# nfc.net
KiCad netlist of a schematic drawn in Altium Designer
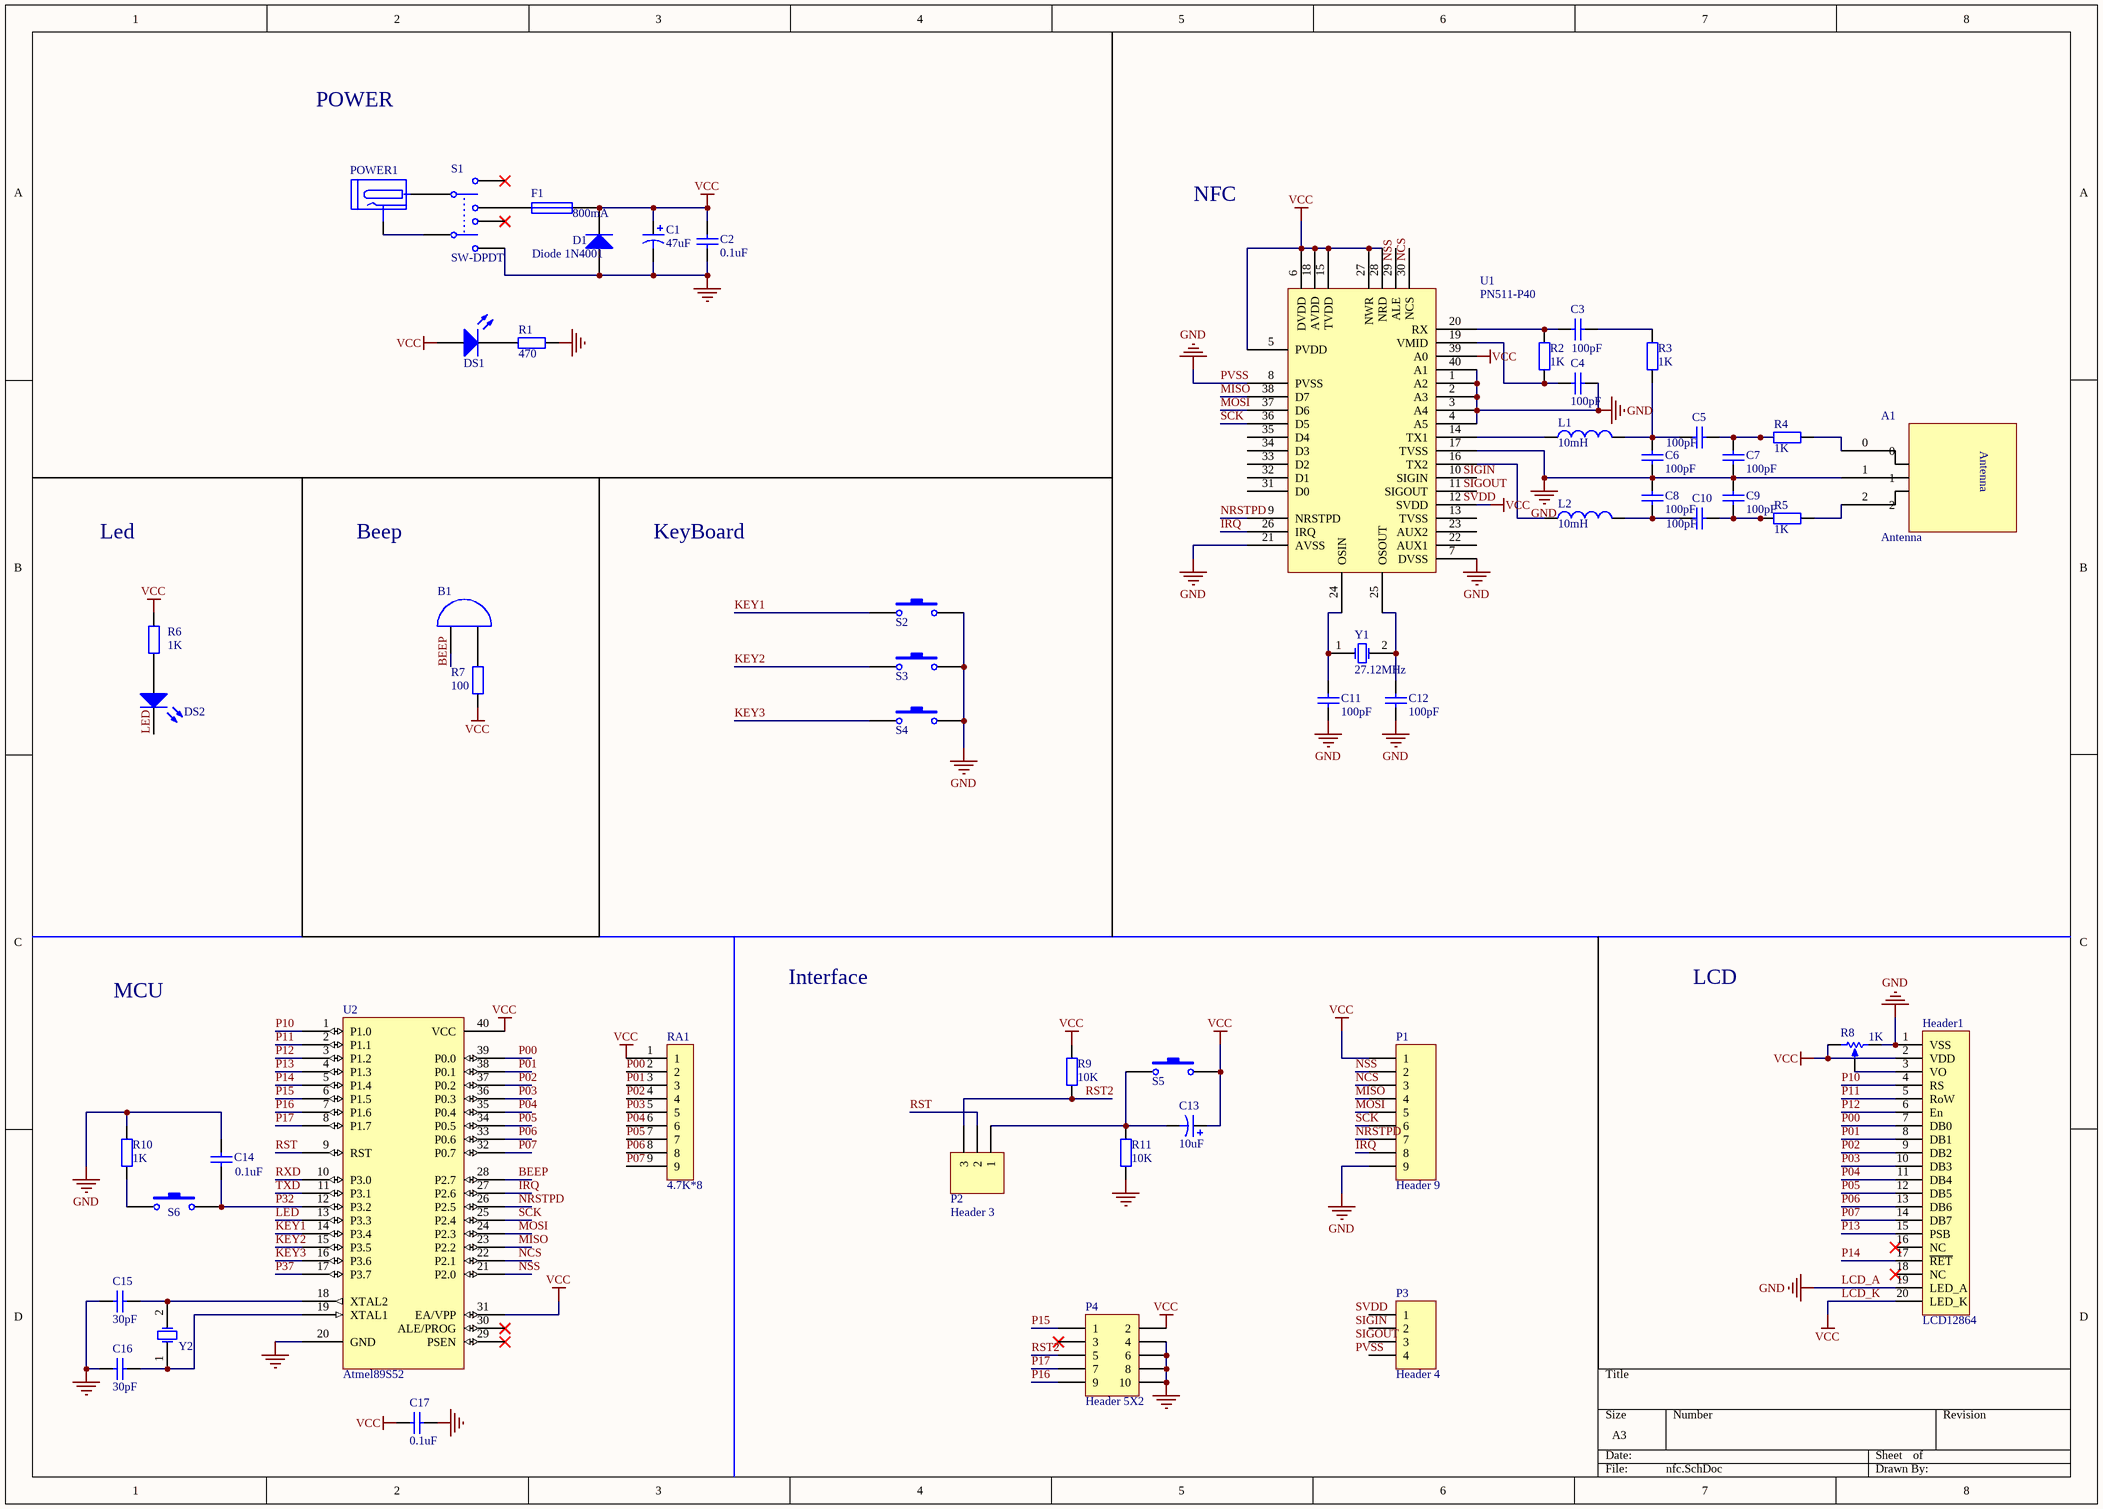
[diagram p0: nfc.SchDoc]

(export (version "E")
  (design (tool "Eeschema 10.0.6"))
  (components
    (comp (ref "A1") (value "Antenna") (libsource (lib "*") (part "Antenna")))
    (comp (ref "B1") (value "BEEP") (footprint "Buzzer") (libsource (lib "51ExpBoard") (part "BEEP")))
    (comp (ref "C1")
      (value "47uF")
      (footprint "51ExpBoard:CAP-LED")
      (description "Polarized Capacitor (Axial)")
      (fields (field (name "Comment") "CAP POL") (field (name "PUBLISHER") "Altium Limited"))
      (libsource (lib "51ExpBoard") (part "CAP POL"))
    )
    (comp (ref "C2")
      (value "0.1uF")
      (footprint "51ExpBoard:CAP")
      (description "Capacitor")
      (fields (field (name "Comment") "Cap") (field (name "PUBLISHER") "Altium Limited"))
      (libsource (lib "51ExpBoard") (part "Cap"))
    )
    (comp (ref "C3")
      (value "100pF")
      (footprint "RAD-0.3")
      (description "Capacitor")
      (fields (field (name "Comment") "Cap") (field (name "PUBLISHER") "Altium Limited"))
      (libsource (lib "Miscellaneous Devices") (part "Cap"))
    )
    (comp (ref "C4")
      (value "100pF")
      (footprint "RAD-0.3")
      (description "Capacitor")
      (fields (field (name "Comment") "Cap") (field (name "PUBLISHER") "Altium Limited"))
      (libsource (lib "Miscellaneous Devices") (part "Cap"))
    )
    (comp (ref "C5")
      (value "100pF")
      (footprint "RAD-0.3")
      (description "Capacitor")
      (fields (field (name "Comment") "Cap") (field (name "PUBLISHER") "Altium Limited"))
      (libsource (lib "Miscellaneous Devices") (part "Cap"))
    )
    (comp (ref "C6")
      (value "100pF")
      (footprint "RAD-0.3")
      (description "Capacitor")
      (fields (field (name "Comment") "Cap") (field (name "PUBLISHER") "Altium Limited"))
      (libsource (lib "Miscellaneous Devices") (part "Cap"))
    )
    (comp (ref "C7")
      (value "100pF")
      (footprint "RAD-0.3")
      (description "Capacitor")
      (fields (field (name "Comment") "Cap") (field (name "PUBLISHER") "Altium Limited"))
      (libsource (lib "Miscellaneous Devices") (part "Cap"))
    )
    (comp (ref "C8")
      (value "100pF")
      (footprint "RAD-0.3")
      (description "Capacitor")
      (fields (field (name "Comment") "Cap") (field (name "PUBLISHER") "Altium Limited"))
      (libsource (lib "Miscellaneous Devices") (part "Cap"))
    )
    (comp (ref "C9")
      (value "100pF")
      (footprint "RAD-0.3")
      (description "Capacitor")
      (fields (field (name "Comment") "Cap") (field (name "PUBLISHER") "Altium Limited"))
      (libsource (lib "Miscellaneous Devices") (part "Cap"))
    )
    (comp (ref "C10")
      (value "100pF")
      (footprint "RAD-0.3")
      (description "Capacitor")
      (fields (field (name "Comment") "Cap") (field (name "PUBLISHER") "Altium Limited"))
      (libsource (lib "Miscellaneous Devices") (part "Cap"))
    )
    (comp (ref "C11")
      (value "100pF")
      (footprint "RAD-0.3")
      (description "Capacitor")
      (fields (field (name "Comment") "Cap") (field (name "PUBLISHER") "Altium Limited"))
      (libsource (lib "Miscellaneous Devices") (part "Cap"))
    )
    (comp (ref "C12")
      (value "100pF")
      (footprint "RAD-0.3")
      (description "Capacitor")
      (fields (field (name "Comment") "Cap") (field (name "PUBLISHER") "Altium Limited"))
      (libsource (lib "Miscellaneous Devices") (part "Cap"))
    )
    (comp (ref "C13")
      (value "10uF")
      (footprint "51ExpBoard:CAP-LED")
      (description "Polarized Capacitor (Axial)")
      (fields (field (name "Comment") "CAP POL") (field (name "PUBLISHER") "Altium Limited"))
      (libsource (lib "51ExpBoard") (part "CAP POL"))
    )
    (comp (ref "C14")
      (value "0.1uF")
      (footprint "VP32-3.2")
      (description "Capacitor")
      (fields (field (name "Comment") "Cap") (field (name "PUBLISHER") "Altium Limited"))
      (libsource (lib "Miscellaneous Devices") (part "Cap"))
    )
    (comp (ref "C15")
      (value "30pF")
      (footprint "51ExpBoard:CAP")
      (description "Capacitor")
      (fields (field (name "Comment") "Cap") (field (name "PUBLISHER") "Altium Limited"))
      (libsource (lib "51ExpBoard") (part "Cap"))
    )
    (comp (ref "C16")
      (value "30pF")
      (footprint "51ExpBoard:CAP")
      (description "Capacitor")
      (fields (field (name "Comment") "Cap") (field (name "PUBLISHER") "Altium Limited"))
      (libsource (lib "51ExpBoard") (part "Cap"))
    )
    (comp (ref "C17")
      (value "0.1uF")
      (footprint "VP32-3.2")
      (description "Capacitor")
      (fields (field (name "Comment") "Cap") (field (name "PUBLISHER") "Altium Limited"))
      (libsource (lib "Miscellaneous Devices") (part "Cap"))
    )
    (comp (ref "D1")
      (value "Diode 1N4001")
      (footprint "DIODE-0.4")
      (description "1 Amp General Purpose Rectifier")
      (fields (field (name "PUBLISHER") "Altium Limited"))
      (libsource (lib "51ExpBoard") (part "Diode 1N4001"))
    )
    (comp (ref "DS1") (value "LED") (footprint "CAP-LED") (libsource (lib "51ExpBoard") (part "LED")))
    (comp (ref "DS2") (value "LED") (footprint "CAP-LED") (libsource (lib "51ExpBoard") (part "LED")))
    (comp (ref "F1")
      (value "800mA")
      (footprint "AXIAL-0.3")
      (fields (field (name "Comment") "FUSE1"))
      (libsource (lib "51ExpBoard") (part "FUSE1"))
    )
    (comp (ref "Header1") (value "LCD12864") (libsource (lib "nfc") (part "LCD12864")))
    (comp (ref "L1")
      (value "10mH")
      (footprint "0402-A")
      (description "Inductor")
      (fields (field (name "PUBLISHER") "Altium Limited"))
      (libsource (lib "Miscellaneous Devices") (part "Inductor"))
    )
    (comp (ref "L2")
      (value "10mH")
      (footprint "0402-A")
      (description "Inductor")
      (fields (field (name "PUBLISHER") "Altium Limited"))
      (libsource (lib "Miscellaneous Devices") (part "Inductor"))
    )
    (comp (ref "P1")
      (value "Header 9")
      (footprint "HDR1X9")
      (description "Header, 9-Pin")
      (fields (field (name "PUBLISHER") "Altium Limited"))
      (libsource (lib "Miscellaneous Connectors") (part "Header 9"))
    )
    (comp (ref "P2")
      (value "Header 3")
      (footprint "HDR1X3")
      (description "Header, 3-Pin")
      (fields (field (name "PUBLISHER") "Altium Limited"))
      (libsource (lib "Miscellaneous Connectors") (part "Header 3"))
    )
    (comp (ref "P3")
      (value "Header 4")
      (footprint "HDR1X4")
      (description "Header, 4-Pin")
      (fields (field (name "PUBLISHER") "Altium Limited"))
      (libsource (lib "Miscellaneous Connectors") (part "Header 4"))
    )
    (comp (ref "P4")
      (value "Header 5X2")
      (footprint "HDR2X5")
      (description "Header, 5-Pin, Dual row")
      (fields (field (name "PUBLISHER") "Altium Limited"))
      (libsource (lib "Miscellaneous Connectors") (part "Header 5X2"))
    )
    (comp (ref "POWER1") (value "POWER") (footprint "Power") (libsource (lib "51ExpBoard") (part "POWER")))
    (comp (ref "R1")
      (value "470")
      (footprint "AXIAL-0.4")
      (description "Resistor")
      (fields (field (name "Comment") "RES") (field (name "PUBLISHER") "Altium Limited"))
      (libsource (lib "") (part "RES_2"))
    )
    (comp (ref "R2")
      (value "1K")
      (footprint "AXIAL-0.4")
      (description "Resistor")
      (fields (field (name "Comment") "Res2") (field (name "PUBLISHER") "Altium Limited"))
      (libsource (lib "Miscellaneous Devices") (part "Res2"))
    )
    (comp (ref "R3")
      (value "1K")
      (footprint "AXIAL-0.4")
      (description "Resistor")
      (fields (field (name "Comment") "Res2") (field (name "PUBLISHER") "Altium Limited"))
      (libsource (lib "Miscellaneous Devices") (part "Res2"))
    )
    (comp (ref "R4")
      (value "1K")
      (footprint "AXIAL-0.4")
      (description "Resistor")
      (fields (field (name "Comment") "Res2") (field (name "PUBLISHER") "Altium Limited"))
      (libsource (lib "") (part "Res2_1"))
    )
    (comp (ref "R5")
      (value "1K")
      (footprint "AXIAL-0.4")
      (description "Resistor")
      (fields (field (name "Comment") "Res2") (field (name "PUBLISHER") "Altium Limited"))
      (libsource (lib "") (part "Res2_1"))
    )
    (comp (ref "R6")
      (value "1K")
      (footprint "AXIAL-0.4")
      (description "Resistor")
      (fields (field (name "Comment") "RES") (field (name "PUBLISHER") "Altium Limited"))
      (libsource (lib "51ExpBoard") (part "RES"))
    )
    (comp (ref "R7")
      (value "100")
      (footprint "AXIAL-0.4")
      (description "Resistor")
      (fields (field (name "Comment") "RES") (field (name "PUBLISHER") "Altium Limited"))
      (libsource (lib "") (part "RES_1"))
    )
    (comp (ref "R8")
      (value "1K")
      (footprint "VR5")
      (description "Potentiometer")
      (fields (field (name "Comment") "RPot") (field (name "PUBLISHER") "Altium Limited"))
      (libsource (lib "Miscellaneous Devices") (part "RPot"))
    )
    (comp (ref "R9")
      (value "10K")
      (footprint "AXIAL-0.4")
      (description "Resistor")
      (fields (field (name "Comment") "RES") (field (name "PUBLISHER") "Altium Limited"))
      (libsource (lib "") (part "RES_1"))
    )
    (comp (ref "R10")
      (value "1K")
      (footprint "AXIAL-0.4")
      (description "Resistor")
      (fields (field (name "Comment") "RES") (field (name "PUBLISHER") "Altium Limited"))
      (libsource (lib "51ExpBoard") (part "RES"))
    )
    (comp (ref "R11")
      (value "10K")
      (footprint "AXIAL-0.4")
      (description "Resistor")
      (fields (field (name "Comment") "RES") (field (name "PUBLISHER") "Altium Limited"))
      (libsource (lib "51ExpBoard") (part "RES"))
    )
    (comp (ref "RA1")
      (value "4.7K*8")
      (footprint "HDR1X9")
      (fields (field (name "Comment") "Res Arry"))
      (libsource (lib "51ExpBoard") (part "Res Arry"))
    )
    (comp (ref "S1")
      (value "SW-DPDT")
      (footprint "SWITCH-6")
      (description "Double-Pole, Double-Throw Switch")
      (fields (field (name "PUBLISHER") "Altium Limited"))
      (libsource (lib "51ExpBoard") (part "SW-DPDT"))
    )
    (comp (ref "S2") (value "SW-PB") (footprint "key") (libsource (lib "51ExpBoard") (part "SW-PB")))
    (comp (ref "S3") (value "SW-PB") (footprint "key") (libsource (lib "51ExpBoard") (part "SW-PB")))
    (comp (ref "S4") (value "SW-PB") (footprint "key") (libsource (lib "51ExpBoard") (part "SW-PB")))
    (comp (ref "S5") (value "SW-PB") (footprint "key") (libsource (lib "51ExpBoard") (part "SW-PB")))
    (comp (ref "S6") (value "SW-PB") (footprint "key") (libsource (lib "51ExpBoard") (part "SW-PB")))
    (comp (ref "U1") (value "PN511-P40") (libsource (lib "*") (part "PN511-P40")))
    (comp (ref "U2")
      (value "Atmel89S52")
      (footprint "ATMEL89S52-DIP40")
      (libsource (lib "51ExpBoard") (part "Atmel89S52"))
    )
    (comp (ref "Y1")
      (value "27.12MHz")
      (footprint "R38")
      (description "Crystal Oscillator")
      (fields (field (name "PUBLISHER") "Altium Limited"))
      (libsource (lib "Miscellaneous Devices") (part "XTAL"))
    )
    (comp (ref "Y2")
      (value "XTAL")
      (footprint "XTAL")
      (description "Crystal Oscillator")
      (fields (field (name "PUBLISHER") "Altium Limited"))
      (libsource (lib "51ExpBoard") (part "XTAL"))
    )
  )
  (nets
    (net (code "1") (name "/BEEP") (class "Default")
      (node (ref "B1") (pin "2") (pinfunction "A_2") (pintype "passive"))
      (node (ref "U2") (pin "28") (pinfunction "P2.7_28") (pintype "bidirectional"))
    )
    (net (code "2") (name "/IRQ") (class "Default")
      (node (ref "P1") (pin "8") (pinfunction "8_8") (pintype "passive"))
      (node (ref "U1") (pin "26") (pinfunction "IRQ_26") (pintype "passive"))
      (node (ref "U2") (pin "27") (pinfunction "P2.6_27") (pintype "bidirectional"))
    )
    (net (code "3") (name "/KEY1") (class "Default")
      (node (ref "S2") (pin "1") (pinfunction "1_1") (pintype "passive"))
      (node (ref "U2") (pin "14") (pinfunction "P3.4_14") (pintype "bidirectional"))
    )
    (net (code "4") (name "/KEY2") (class "Default")
      (node (ref "S3") (pin "1") (pinfunction "1_1") (pintype "passive"))
      (node (ref "U2") (pin "15") (pinfunction "P3.5_15") (pintype "bidirectional"))
    )
    (net (code "5") (name "/KEY3") (class "Default")
      (node (ref "S4") (pin "1") (pinfunction "1_1") (pintype "passive"))
      (node (ref "U2") (pin "16") (pinfunction "P3.6_16") (pintype "bidirectional"))
    )
    (net (code "6") (name "/LED") (class "Default")
      (node (ref "DS2") (pin "2") (pinfunction "K_2") (pintype "passive"))
      (node (ref "U2") (pin "13") (pinfunction "P3.3_13") (pintype "bidirectional"))
    )
    (net (code "7") (name "/MISO") (class "Default")
      (node (ref "P1") (pin "4") (pinfunction "4_4") (pintype "passive"))
      (node (ref "U1") (pin "38") (pinfunction "D7_38") (pintype "passive"))
      (node (ref "U2") (pin "23") (pinfunction "P2.2_23") (pintype "bidirectional"))
    )
    (net (code "8") (name "/MOSI") (class "Default")
      (node (ref "P1") (pin "5") (pinfunction "5_5") (pintype "passive"))
      (node (ref "U1") (pin "37") (pinfunction "D6_37") (pintype "passive"))
      (node (ref "U2") (pin "24") (pinfunction "P2.3_24") (pintype "bidirectional"))
    )
    (net (code "9") (name "/NCS") (class "Default")
      (node (ref "P1") (pin "3") (pinfunction "3_3") (pintype "passive"))
      (node (ref "U2") (pin "22") (pinfunction "P2.1_22") (pintype "bidirectional"))
    )
    (net (code "10") (name "/NRSTPD") (class "Default")
      (node (ref "P1") (pin "7") (pinfunction "7_7") (pintype "passive"))
      (node (ref "U1") (pin "9") (pinfunction "NRSTPD_9") (pintype "passive"))
      (node (ref "U2") (pin "26") (pinfunction "P2.5_26") (pintype "bidirectional"))
    )
    (net (code "11") (name "/NSS") (class "Default")
      (node (ref "P1") (pin "2") (pinfunction "2_2") (pintype "passive"))
      (node (ref "U2") (pin "21") (pinfunction "P2.0_21") (pintype "bidirectional"))
    )
    (net (code "12") (name "/P00") (class "Default")
      (node (ref "Header1") (pin "7") (pinfunction "DB0_7") (pintype "passive"))
      (node (ref "RA1") (pin "2") (pinfunction "2_2") (pintype "passive"))
      (node (ref "U2") (pin "39") (pinfunction "P0.0_39") (pintype "bidirectional"))
    )
    (net (code "13") (name "/P01") (class "Default")
      (node (ref "Header1") (pin "8") (pinfunction "DB1_8") (pintype "passive"))
      (node (ref "RA1") (pin "3") (pinfunction "3_3") (pintype "passive"))
      (node (ref "U2") (pin "38") (pinfunction "P0.1_38") (pintype "bidirectional"))
    )
    (net (code "14") (name "/P02") (class "Default")
      (node (ref "Header1") (pin "9") (pinfunction "DB2_9") (pintype "passive"))
      (node (ref "RA1") (pin "4") (pinfunction "4_4") (pintype "passive"))
      (node (ref "U2") (pin "37") (pinfunction "P0.2_37") (pintype "bidirectional"))
    )
    (net (code "15") (name "/P03") (class "Default")
      (node (ref "Header1") (pin "10") (pinfunction "DB3_10") (pintype "passive"))
      (node (ref "RA1") (pin "5") (pinfunction "5_5") (pintype "passive"))
      (node (ref "U2") (pin "36") (pinfunction "P0.3_36") (pintype "bidirectional"))
    )
    (net (code "16") (name "/P04") (class "Default")
      (node (ref "Header1") (pin "11") (pinfunction "DB4_11") (pintype "passive"))
      (node (ref "RA1") (pin "6") (pinfunction "6_6") (pintype "passive"))
      (node (ref "U2") (pin "35") (pinfunction "P0.4_35") (pintype "bidirectional"))
    )
    (net (code "17") (name "/P05") (class "Default")
      (node (ref "Header1") (pin "12") (pinfunction "DB5_12") (pintype "passive"))
      (node (ref "RA1") (pin "7") (pinfunction "7_7") (pintype "passive"))
      (node (ref "U2") (pin "34") (pinfunction "P0.5_34") (pintype "bidirectional"))
    )
    (net (code "18") (name "/P06") (class "Default")
      (node (ref "Header1") (pin "13") (pinfunction "DB6_13") (pintype "passive"))
      (node (ref "RA1") (pin "8") (pinfunction "8_8") (pintype "passive"))
      (node (ref "U2") (pin "33") (pinfunction "P0.6_33") (pintype "bidirectional"))
    )
    (net (code "19") (name "/P07") (class "Default")
      (node (ref "Header1") (pin "14") (pinfunction "DB7_14") (pintype "passive"))
      (node (ref "RA1") (pin "9") (pinfunction "9_9") (pintype "passive"))
      (node (ref "U2") (pin "32") (pinfunction "P0.7_32") (pintype "bidirectional"))
    )
    (net (code "20") (name "/P10") (class "Default")
      (node (ref "Header1") (pin "4") (pinfunction "RS_4") (pintype "passive"))
      (node (ref "U2") (pin "1") (pinfunction "P1.0_1") (pintype "bidirectional"))
    )
    (net (code "21") (name "/P11") (class "Default")
      (node (ref "Header1") (pin "5") (pinfunction "RoW_5") (pintype "passive"))
      (node (ref "U2") (pin "2") (pinfunction "P1.1_2") (pintype "bidirectional"))
    )
    (net (code "22") (name "/P12") (class "Default")
      (node (ref "Header1") (pin "6") (pinfunction "En_6") (pintype "passive"))
      (node (ref "U2") (pin "3") (pinfunction "P1.2_3") (pintype "bidirectional"))
    )
    (net (code "23") (name "/P13") (class "Default")
      (node (ref "Header1") (pin "15") (pinfunction "PSB_15") (pintype "passive"))
      (node (ref "U2") (pin "4") (pinfunction "P1.3_4") (pintype "bidirectional"))
    )
    (net (code "24") (name "/P14") (class "Default")
      (node (ref "Header1") (pin "17") (pinfunction "~{RET}_17") (pintype "passive"))
      (node (ref "U2") (pin "5") (pinfunction "P1.4_5") (pintype "bidirectional"))
    )
    (net (code "25") (name "/P15") (class "Default")
      (node (ref "P4") (pin "1") (pinfunction "1_1") (pintype "passive"))
      (node (ref "U2") (pin "6") (pinfunction "P1.5_6") (pintype "bidirectional"))
    )
    (net (code "26") (name "/P16") (class "Default")
      (node (ref "P4") (pin "9") (pinfunction "9_9") (pintype "passive"))
      (node (ref "U2") (pin "7") (pinfunction "P1.6_7") (pintype "bidirectional"))
    )
    (net (code "27") (name "/P17") (class "Default")
      (node (ref "P4") (pin "7") (pinfunction "7_7") (pintype "passive"))
      (node (ref "U2") (pin "8") (pinfunction "P1.7_8") (pintype "bidirectional"))
    )
    (net (code "28") (name "/P32") (class "Default")
      (node (ref "C14") (pin "1") (pinfunction "1_1") (pintype "passive"))
      (node (ref "S6") (pin "2") (pinfunction "2_2") (pintype "passive"))
      (node (ref "U2") (pin "12") (pinfunction "P3.2_12") (pintype "bidirectional"))
    )
    (net (code "29") (name "/P37") (class "Default")
      (node (ref "U2") (pin "17") (pinfunction "P3.7_17") (pintype "bidirectional"))
    )
    (net (code "30") (name "/RST") (class "Default")
      (node (ref "P2") (pin "2") (pinfunction "2_2") (pintype "passive"))
      (node (ref "U2") (pin "9") (pinfunction "RST_9") (pintype "bidirectional"))
    )
    (net (code "31") (name "/RST2") (class "Default")
      (node (ref "P2") (pin "3") (pinfunction "3_3") (pintype "passive"))
      (node (ref "P4") (pin "5") (pinfunction "5_5") (pintype "passive"))
      (node (ref "R9") (pin "2") (pinfunction "2_2") (pintype "passive"))
    )
    (net (code "32") (name "/RXD") (class "Default")
      (node (ref "U2") (pin "10") (pinfunction "P3.0_10") (pintype "bidirectional"))
    )
    (net (code "33") (name "/SCK") (class "Default")
      (node (ref "P1") (pin "6") (pinfunction "6_6") (pintype "passive"))
      (node (ref "U1") (pin "36") (pinfunction "D5_36") (pintype "passive"))
      (node (ref "U2") (pin "25") (pinfunction "P2.4_25") (pintype "bidirectional"))
    )
    (net (code "37") (name "/TXD") (class "Default")
      (node (ref "U2") (pin "11") (pinfunction "P3.1_11") (pintype "bidirectional"))
    )
    (net (code "38") (name "GND") (class "Default")
      (node (ref "A1") (pin "1") (pinfunction "1_1") (pintype "passive"))
      (node (ref "C1") (pin "2") (pinfunction "2_2") (pintype "passive"))
      (node (ref "C11") (pin "1") (pinfunction "1_1") (pintype "passive"))
      (node (ref "C12") (pin "1") (pinfunction "1_1") (pintype "passive"))
      (node (ref "C14") (pin "2") (pinfunction "2_2") (pintype "passive"))
      (node (ref "C15") (pin "1") (pinfunction "1_1") (pintype "passive"))
      (node (ref "C16") (pin "1") (pinfunction "1_1") (pintype "passive"))
      (node (ref "C17") (pin "2") (pinfunction "2_2") (pintype "passive"))
      (node (ref "C2") (pin "2") (pinfunction "2_2") (pintype "passive"))
      (node (ref "C4") (pin "2") (pinfunction "2_2") (pintype "passive"))
      (node (ref "C6") (pin "1") (pinfunction "1_1") (pintype "passive"))
      (node (ref "C7") (pin "1") (pinfunction "1_1") (pintype "passive"))
      (node (ref "C8") (pin "2") (pinfunction "2_2") (pintype "passive"))
      (node (ref "C9") (pin "2") (pinfunction "2_2") (pintype "passive"))
      (node (ref "D1") (pin "1") (pinfunction "A_1") (pintype "passive"))
      (node (ref "Header1") (pin "1") (pinfunction "VSS_1") (pintype "passive"))
      (node (ref "Header1") (pin "19") (pinfunction "LED_A_19") (pintype "passive"))
      (node (ref "P1") (pin "9") (pinfunction "9_9") (pintype "passive"))
      (node (ref "P4") (pin "10") (pinfunction "10_10") (pintype "passive"))
      (node (ref "P4") (pin "4") (pinfunction "4_4") (pintype "passive"))
      (node (ref "P4") (pin "6") (pinfunction "6_6") (pintype "passive"))
      (node (ref "P4") (pin "8") (pinfunction "8_8") (pintype "passive"))
      (node (ref "R1") (pin "2") (pinfunction "2_2") (pintype "passive"))
      (node (ref "R10") (pin "2") (pinfunction "2_2") (pintype "passive"))
      (node (ref "R11") (pin "1") (pinfunction "1_1") (pintype "passive"))
      (node (ref "R8") (pin "2") (pinfunction "BOT_2") (pintype "passive"))
      (node (ref "S1") (pin "6") (pinfunction "6_6") (pintype "passive"))
      (node (ref "S2") (pin "2") (pinfunction "2_2") (pintype "passive"))
      (node (ref "S3") (pin "2") (pinfunction "2_2") (pintype "passive"))
      (node (ref "S4") (pin "2") (pinfunction "2_2") (pintype "passive"))
      (node (ref "U1") (pin "1") (pinfunction "A2_1") (pintype "passive"))
      (node (ref "U1") (pin "17") (pinfunction "TVSS_17") (pintype "passive"))
      (node (ref "U1") (pin "2") (pinfunction "A3_2") (pintype "passive"))
      (node (ref "U1") (pin "21") (pinfunction "AVSS_21") (pintype "passive"))
      (node (ref "U1") (pin "3") (pinfunction "A4_3") (pintype "passive"))
      (node (ref "U1") (pin "4") (pinfunction "A5_4") (pintype "passive"))
      (node (ref "U1") (pin "40") (pinfunction "A1_40") (pintype "passive"))
      (node (ref "U1") (pin "7") (pinfunction "DVSS_7") (pintype "passive"))
      (node (ref "U1") (pin "8") (pinfunction "PVSS_8") (pintype "passive"))
      (node (ref "U2") (pin "20") (pinfunction "GND_20") (pintype "power_in"))
    )
    (net (code "39") (name "Net-(A1-Pad0)") (class "Default")
      (node (ref "A1") (pin "0") (pinfunction "0_0") (pintype "passive"))
      (node (ref "R4") (pin "1") (pinfunction "1_1") (pintype "passive"))
    )
    (net (code "40") (name "Net-(A1-Pad2)") (class "Default")
      (node (ref "A1") (pin "2") (pinfunction "2_2") (pintype "passive"))
      (node (ref "R5") (pin "1") (pinfunction "1_1") (pintype "passive"))
    )
    (net (code "41") (name "Net-(B1-B)") (class "Default")
      (node (ref "B1") (pin "1") (pinfunction "B_1") (pintype "passive"))
      (node (ref "R7") (pin "1") (pinfunction "1_1") (pintype "passive"))
    )
    (net (code "42") (name "Net-(C3-Pad2)") (class "Default")
      (node (ref "C3") (pin "2") (pinfunction "2_2") (pintype "passive"))
      (node (ref "R3") (pin "2") (pinfunction "2_2") (pintype "passive"))
    )
    (net (code "43") (name "Net-(C5-Pad1)") (class "Default")
      (node (ref "C5") (pin "1") (pinfunction "1_1") (pintype "passive"))
      (node (ref "C6") (pin "2") (pinfunction "2_2") (pintype "passive"))
      (node (ref "L1") (pin "2") (pinfunction "2_2") (pintype "passive"))
      (node (ref "R3") (pin "1") (pinfunction "1_1") (pintype "passive"))
    )
    (net (code "44") (name "Net-(C5-Pad2)") (class "Default")
      (node (ref "C5") (pin "2") (pinfunction "2_2") (pintype "passive"))
      (node (ref "C7") (pin "2") (pinfunction "2_2") (pintype "passive"))
      (node (ref "R4") (pin "2") (pinfunction "2_2") (pintype "passive"))
    )
    (net (code "45") (name "Net-(C10-Pad1)") (class "Default")
      (node (ref "C10") (pin "1") (pinfunction "1_1") (pintype "passive"))
      (node (ref "C8") (pin "1") (pinfunction "1_1") (pintype "passive"))
      (node (ref "L2") (pin "2") (pinfunction "2_2") (pintype "passive"))
    )
    (net (code "46") (name "Net-(C10-Pad2)") (class "Default")
      (node (ref "C10") (pin "2") (pinfunction "2_2") (pintype "passive"))
      (node (ref "C9") (pin "1") (pinfunction "1_1") (pintype "passive"))
      (node (ref "R5") (pin "2") (pinfunction "2_2") (pintype "passive"))
    )
    (net (code "47") (name "Net-(C13-Pad2)") (class "Default")
      (node (ref "C13") (pin "2") (pinfunction "2_2") (pintype "passive"))
      (node (ref "P2") (pin "1") (pinfunction "1_1") (pintype "passive"))
      (node (ref "R11") (pin "2") (pinfunction "2_2") (pintype "passive"))
      (node (ref "S5") (pin "1") (pinfunction "1_1") (pintype "passive"))
    )
    (net (code "48") (name "Net-(DS1-K)") (class "Default")
      (node (ref "DS1") (pin "2") (pinfunction "K_2") (pintype "passive"))
      (node (ref "R1") (pin "1") (pinfunction "1_1") (pintype "passive"))
    )
    (net (code "49") (name "Net-(DS2-A)") (class "Default")
      (node (ref "DS2") (pin "1") (pinfunction "A_1") (pintype "passive"))
      (node (ref "R6") (pin "1") (pinfunction "1_1") (pintype "passive"))
    )
    (net (code "50") (name "Net-(F1-Pad1)") (class "Default")
      (node (ref "F1") (pin "1") (pinfunction "1_1") (pintype "passive"))
      (node (ref "S1") (pin "3") (pinfunction "3_3") (pintype "passive"))
    )
    (net (code "51") (name "Net-(Header1-VO)") (class "Default")
      (node (ref "Header1") (pin "3") (pinfunction "VO_3") (pintype "passive"))
      (node (ref "R8") (pin "3") (pinfunction "TAP_3") (pintype "passive"))
    )
    (net (code "52") (name "Net-(POWER1-Pad1)") (class "Default")
      (node (ref "POWER1") (pin "1") (pinfunction "1_1") (pintype "power_in"))
      (node (ref "S1") (pin "1") (pinfunction "1_1") (pintype "passive"))
    )
    (net (code "53") (name "Net-(POWER1-Pad2)") (class "Default")
      (node (ref "POWER1") (pin "2") (pinfunction "2_2") (pintype "power_in"))
      (node (ref "S1") (pin "4") (pinfunction "4_4") (pintype "passive"))
    )
    (net (code "54") (name "Net-(R10-Pad1)") (class "Default")
      (node (ref "R10") (pin "1") (pinfunction "1_1") (pintype "passive"))
      (node (ref "S6") (pin "1") (pinfunction "1_1") (pintype "passive"))
    )
    (net (code "55") (name "Net-(U1-OSIN)") (class "Default")
      (node (ref "C11") (pin "2") (pinfunction "2_2") (pintype "passive"))
      (node (ref "U1") (pin "24") (pinfunction "OSIN_24") (pintype "passive"))
      (node (ref "Y1") (pin "1") (pinfunction "OSC1_1") (pintype "passive"))
    )
    (net (code "56") (name "Net-(U1-OSOUT)") (class "Default")
      (node (ref "C12") (pin "2") (pinfunction "2_2") (pintype "passive"))
      (node (ref "U1") (pin "25") (pinfunction "OSOUT_25") (pintype "passive"))
      (node (ref "Y1") (pin "2") (pinfunction "OSC2_2") (pintype "passive"))
    )
    (net (code "57") (name "Net-(U1-RX)") (class "Default")
      (node (ref "C3") (pin "1") (pinfunction "1_1") (pintype "passive"))
      (node (ref "R2") (pin "2") (pinfunction "2_2") (pintype "passive"))
      (node (ref "U1") (pin "20") (pinfunction "RX_20") (pintype "passive"))
    )
    (net (code "58") (name "Net-(U1-TX1)") (class "Default")
      (node (ref "L1") (pin "1") (pinfunction "1_1") (pintype "passive"))
      (node (ref "U1") (pin "14") (pinfunction "TX1_14") (pintype "passive"))
    )
    (net (code "59") (name "Net-(U1-TX2)") (class "Default")
      (node (ref "L2") (pin "1") (pinfunction "1_1") (pintype "passive"))
      (node (ref "U1") (pin "16") (pinfunction "TX2_16") (pintype "passive"))
    )
    (net (code "60") (name "Net-(U1-VMID)") (class "Default")
      (node (ref "C4") (pin "1") (pinfunction "1_1") (pintype "passive"))
      (node (ref "R2") (pin "1") (pinfunction "1_1") (pintype "passive"))
      (node (ref "U1") (pin "19") (pinfunction "VMID_19") (pintype "passive"))
    )
    (net (code "61") (name "Net-(U2-XTAL1)") (class "Default")
      (node (ref "C16") (pin "2") (pinfunction "2_2") (pintype "passive"))
      (node (ref "U2") (pin "19") (pinfunction "XTAL1_19") (pintype "input"))
      (node (ref "Y2") (pin "1") (pinfunction "OSC1_1") (pintype "passive"))
    )
    (net (code "62") (name "Net-(U2-XTAL2)") (class "Default")
      (node (ref "C15") (pin "2") (pinfunction "2_2") (pintype "passive"))
      (node (ref "U2") (pin "18") (pinfunction "XTAL2_18") (pintype "output"))
      (node (ref "Y2") (pin "2") (pinfunction "OSC2_2") (pintype "passive"))
    )
    (net (code "63") (name "VCC") (class "Default")
      (node (ref "C1") (pin "1") (pinfunction "1_1") (pintype "passive"))
      (node (ref "C13") (pin "1") (pinfunction "1_1") (pintype "passive"))
      (node (ref "C17") (pin "1") (pinfunction "1_1") (pintype "passive"))
      (node (ref "C2") (pin "1") (pinfunction "1_1") (pintype "passive"))
      (node (ref "D1") (pin "2") (pinfunction "K_2") (pintype "passive"))
      (node (ref "DS1") (pin "1") (pinfunction "A_1") (pintype "passive"))
      (node (ref "F1") (pin "2") (pinfunction "2_2") (pintype "passive"))
      (node (ref "Header1") (pin "2") (pinfunction "VDD_2") (pintype "passive"))
      (node (ref "Header1") (pin "20") (pinfunction "LED_K_20") (pintype "passive"))
      (node (ref "P1") (pin "1") (pinfunction "1_1") (pintype "passive"))
      (node (ref "P4") (pin "2") (pinfunction "2_2") (pintype "passive"))
      (node (ref "R6") (pin "2") (pinfunction "2_2") (pintype "passive"))
      (node (ref "R7") (pin "2") (pinfunction "2_2") (pintype "passive"))
      (node (ref "R8") (pin "1") (pinfunction "TOP_1") (pintype "passive"))
      (node (ref "R9") (pin "1") (pinfunction "1_1") (pintype "passive"))
      (node (ref "RA1") (pin "1") (pinfunction "1_1") (pintype "passive"))
      (node (ref "S5") (pin "2") (pinfunction "2_2") (pintype "passive"))
      (node (ref "U1") (pin "12") (pinfunction "SVDD_12") (pintype "passive"))
      (node (ref "U1") (pin "15") (pinfunction "TVDD_15") (pintype "passive"))
      (node (ref "U1") (pin "18") (pinfunction "AVDD_18") (pintype "passive"))
      (node (ref "U1") (pin "27") (pinfunction "NWR_27") (pintype "passive"))
      (node (ref "U1") (pin "28") (pinfunction "NRD_28") (pintype "passive"))
      (node (ref "U1") (pin "39") (pinfunction "A0_39") (pintype "passive"))
      (node (ref "U1") (pin "5") (pinfunction "PVDD_5") (pintype "passive"))
      (node (ref "U1") (pin "6") (pinfunction "DVDD_6") (pintype "passive"))
      (node (ref "U2") (pin "31") (pinfunction "EA/VPP_31") (pintype "bidirectional"))
      (node (ref "U2") (pin "40") (pinfunction "VCC_40") (pintype "power_in"))
    )
    (net (code "64") (name "unconnected-(Header1-NC-Pad16)") (class "Default")
      (node (ref "Header1") (pin "16") (pinfunction "NC_16") (pintype "passive+no_connect"))
    )
    (net (code "65") (name "unconnected-(Header1-NC-Pad18)") (class "Default")
      (node (ref "Header1") (pin "18") (pinfunction "NC_18") (pintype "passive+no_connect"))
    )
    (net (code "66") (name "unconnected-(P3-Pad1)") (class "Default")
      (node (ref "P3") (pin "1") (pinfunction "1_1") (pintype "passive"))
    )
    (net (code "67") (name "unconnected-(P3-Pad2)") (class "Default")
      (node (ref "P3") (pin "2") (pinfunction "2_2") (pintype "passive"))
    )
    (net (code "68") (name "unconnected-(P3-Pad3)") (class "Default")
      (node (ref "P3") (pin "3") (pinfunction "3_3") (pintype "passive"))
    )
    (net (code "69") (name "unconnected-(P3-Pad4)") (class "Default")
      (node (ref "P3") (pin "4") (pinfunction "4_4") (pintype "passive"))
    )
    (net (code "70") (name "unconnected-(P4-Pad3)") (class "Default")
      (node (ref "P4") (pin "3") (pinfunction "3_3") (pintype "passive+no_connect"))
    )
    (net (code "71") (name "unconnected-(S1-Pad2)") (class "Default")
      (node (ref "S1") (pin "2") (pinfunction "2_2") (pintype "passive+no_connect"))
    )
    (net (code "72") (name "unconnected-(S1-Pad5)") (class "Default")
      (node (ref "S1") (pin "5") (pinfunction "5_5") (pintype "passive+no_connect"))
    )
    (net (code "73") (name "unconnected-(U1-ALE-Pad29)") (class "Default")
      (node (ref "U1") (pin "29") (pinfunction "ALE_29") (pintype "passive"))
    )
    (net (code "74") (name "unconnected-(U1-AUX1-Pad22)") (class "Default")
      (node (ref "U1") (pin "22") (pinfunction "AUX1_22") (pintype "passive"))
    )
    (net (code "75") (name "unconnected-(U1-AUX2-Pad23)") (class "Default")
      (node (ref "U1") (pin "23") (pinfunction "AUX2_23") (pintype "passive"))
    )
    (net (code "76") (name "unconnected-(U1-D0-Pad31)") (class "Default")
      (node (ref "U1") (pin "31") (pinfunction "D0_31") (pintype "passive"))
    )
    (net (code "77") (name "unconnected-(U1-D1-Pad32)") (class "Default")
      (node (ref "U1") (pin "32") (pinfunction "D1_32") (pintype "passive"))
    )
    (net (code "78") (name "unconnected-(U1-D2-Pad33)") (class "Default")
      (node (ref "U1") (pin "33") (pinfunction "D2_33") (pintype "passive"))
    )
    (net (code "79") (name "unconnected-(U1-D3-Pad34)") (class "Default")
      (node (ref "U1") (pin "34") (pinfunction "D3_34") (pintype "passive"))
    )
    (net (code "80") (name "unconnected-(U1-D4-Pad35)") (class "Default")
      (node (ref "U1") (pin "35") (pinfunction "D4_35") (pintype "passive"))
    )
    (net (code "81") (name "unconnected-(U1-NCS-Pad30)") (class "Default")
      (node (ref "U1") (pin "30") (pinfunction "NCS_30") (pintype "passive"))
    )
    (net (code "82") (name "unconnected-(U1-SIGIN-Pad10)") (class "Default")
      (node (ref "U1") (pin "10") (pinfunction "SIGIN_10") (pintype "passive"))
    )
    (net (code "83") (name "unconnected-(U1-SIGOUT-Pad11)") (class "Default")
      (node (ref "U1") (pin "11") (pinfunction "SIGOUT_11") (pintype "passive"))
    )
    (net (code "84") (name "unconnected-(U1-TVSS-Pad13)") (class "Default")
      (node (ref "U1") (pin "13") (pinfunction "TVSS_13") (pintype "passive"))
    )
    (net (code "85") (name "unconnected-(U2-ALE{slash}PROG-Pad30)") (class "Default")
      (node (ref "U2") (pin "30") (pinfunction "ALE/PROG_30") (pintype "bidirectional+no_connect"))
    )
    (net (code "86") (name "unconnected-(U2-PSEN-Pad29)") (class "Default")
      (node (ref "U2") (pin "29") (pinfunction "PSEN_29") (pintype "bidirectional+no_connect"))
    )
  )
)
